# VS1053_hardware.net
KiCad netlist of a schematic drawn in EAGLE
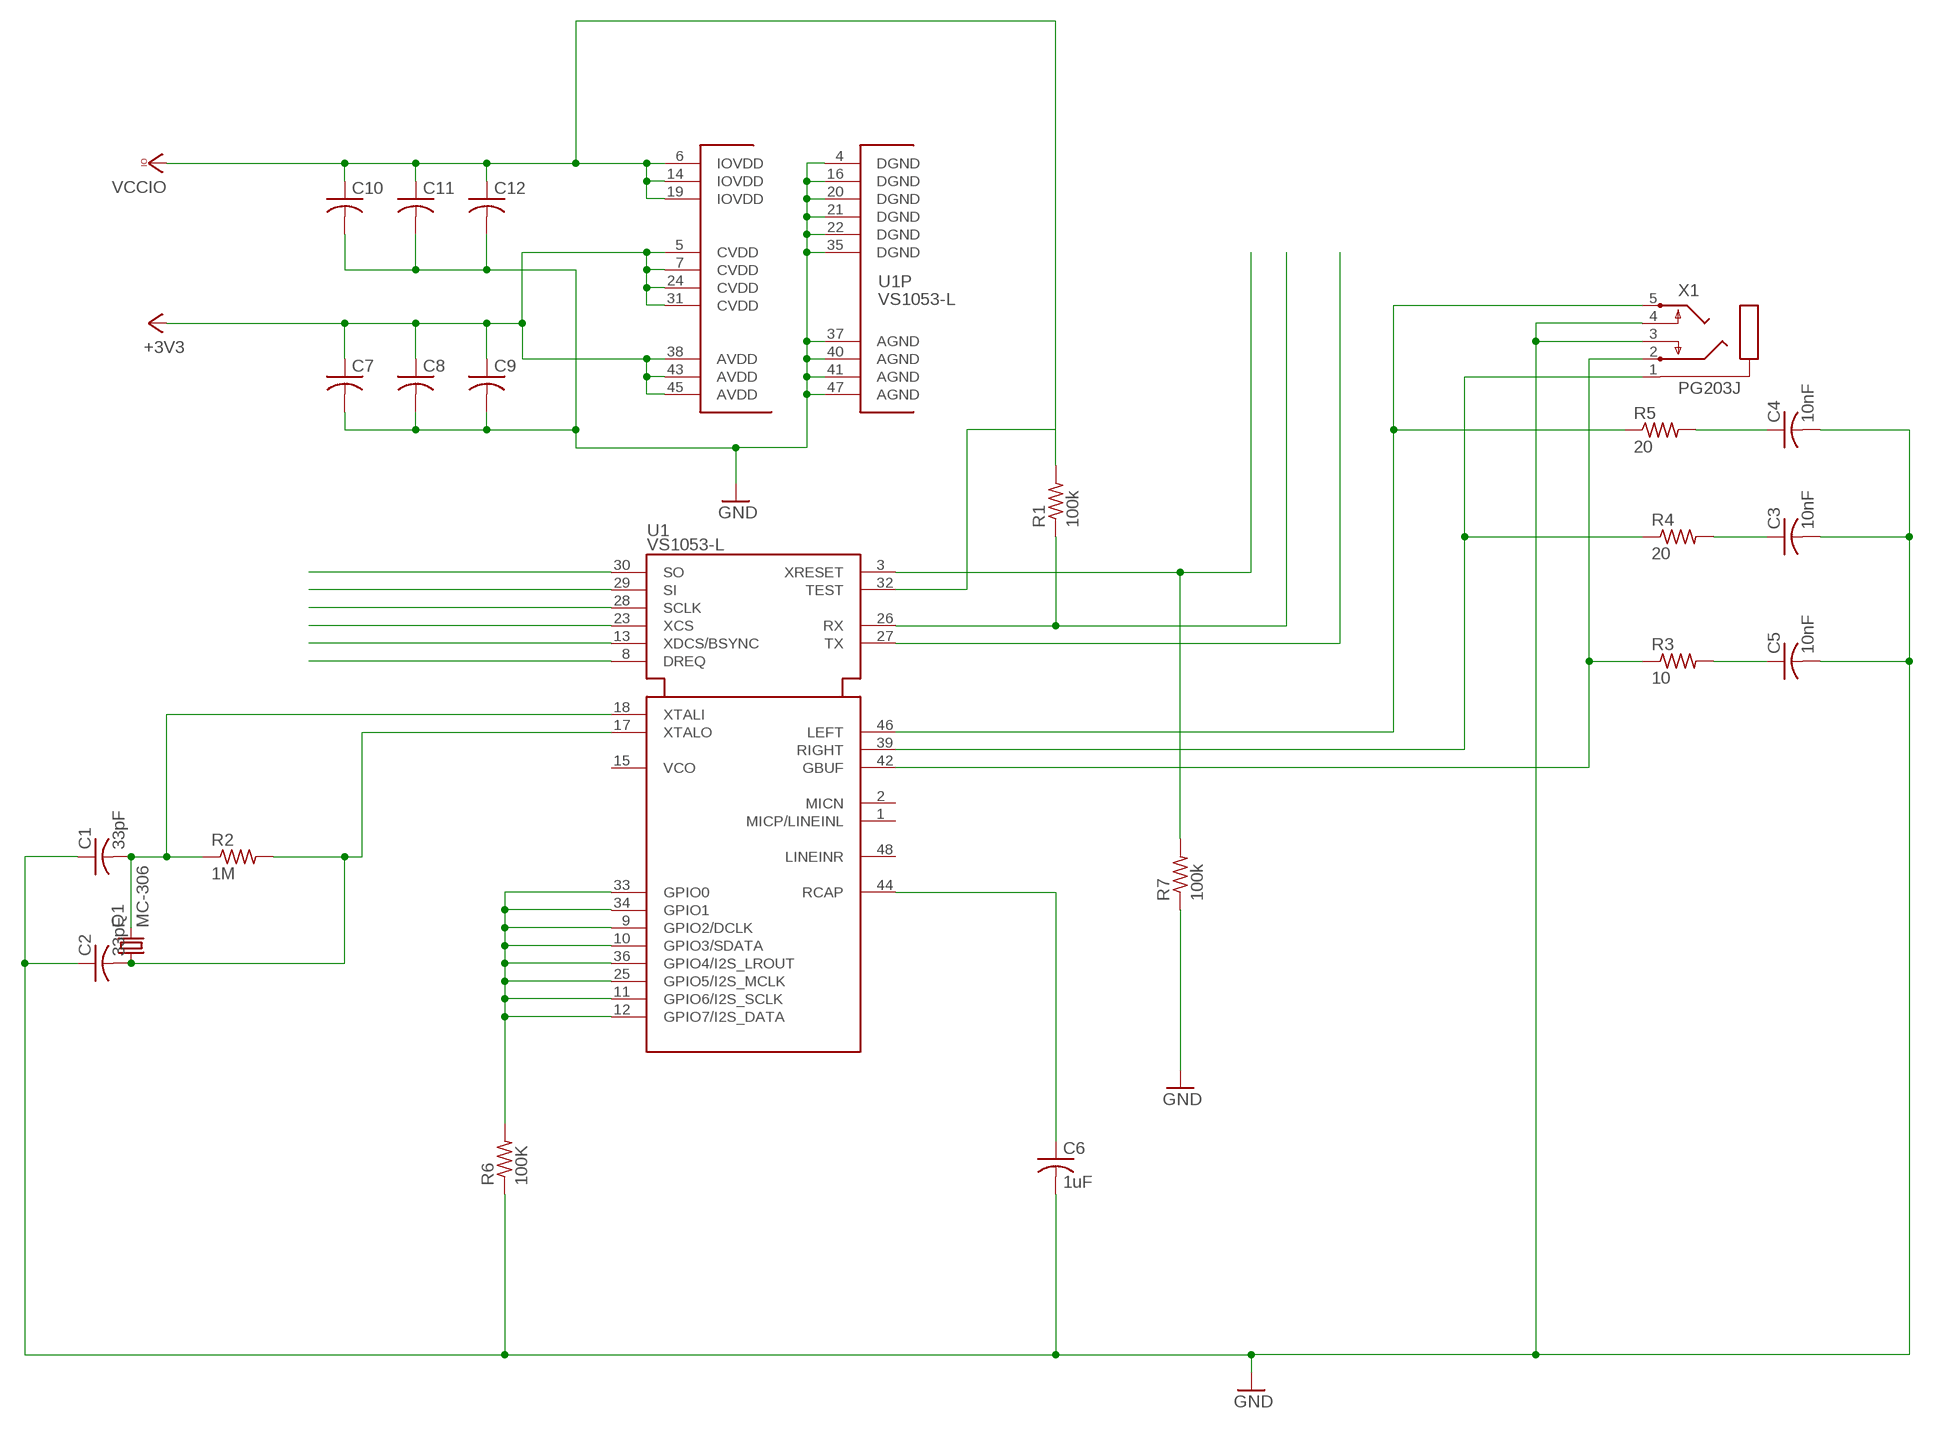
[diagram p0: schematic, sheet 1]

(export (version "E")
  (design (tool "Eeschema 10.0.6"))
  (components
    (comp (ref "C1")
      (value "33pF")
      (footprint "eagle-import:C0402")
      (libsource (lib "eagle-import") (part "C-USC0402"))
    )
    (comp (ref "C2")
      (value "33pF")
      (footprint "eagle-import:C0402")
      (libsource (lib "eagle-import") (part "C-USC0402"))
    )
    (comp (ref "C3")
      (value "10nF")
      (footprint "eagle-import:C0201")
      (libsource (lib "eagle-import") (part "C-USC0201"))
    )
    (comp (ref "C4")
      (value "10nF")
      (footprint "eagle-import:C0201")
      (libsource (lib "eagle-import") (part "C-USC0201"))
    )
    (comp (ref "C5")
      (value "10nF")
      (footprint "eagle-import:C0201")
      (libsource (lib "eagle-import") (part "C-USC0201"))
    )
    (comp (ref "C6")
      (value "1uF")
      (footprint "eagle-import:C0201")
      (libsource (lib "eagle-import") (part "C-USC0201"))
    )
    (comp (ref "C7")
      (value "C-USC0504")
      (footprint "eagle-import:C0504")
      (libsource (lib "eagle-import") (part "C-USC0504"))
    )
    (comp (ref "C8")
      (value "C-USC0504")
      (footprint "eagle-import:C0504")
      (libsource (lib "eagle-import") (part "C-USC0504"))
    )
    (comp (ref "C9")
      (value "C-USC0504")
      (footprint "eagle-import:C0504")
      (libsource (lib "eagle-import") (part "C-USC0504"))
    )
    (comp (ref "C10")
      (value "C-USC0504")
      (footprint "eagle-import:C0504")
      (libsource (lib "eagle-import") (part "C-USC0504"))
    )
    (comp (ref "C11")
      (value "C-USC0504")
      (footprint "eagle-import:C0504")
      (libsource (lib "eagle-import") (part "C-USC0504"))
    )
    (comp (ref "C12")
      (value "C-USC0504")
      (footprint "eagle-import:C0504")
      (libsource (lib "eagle-import") (part "C-USC0504"))
    )
    (comp (ref "Q1")
      (value "MC-306")
      (footprint "eagle-import:MC-306")
      (fields (field (name "MPN") "MC-306 60.0KHZ  100PPM ,12.5PF"))
      (libsource (lib "eagle-import") (part "MC-306"))
    )
    (comp (ref "R1")
      (value "100k")
      (footprint "eagle-import:M0805")
      (libsource (lib "eagle-import") (part "R-US_M0805"))
    )
    (comp (ref "R2")
      (value "1M")
      (footprint "eagle-import:1812X7R")
      (libsource (lib "eagle-import") (part "R-US_1812X7R"))
    )
    (comp (ref "R3")
      (value "10")
      (footprint "eagle-import:R01005")
      (libsource (lib "eagle-import") (part "R-US_01005"))
    )
    (comp (ref "R4")
      (value "20")
      (footprint "eagle-import:R01005")
      (libsource (lib "eagle-import") (part "R-US_01005"))
    )
    (comp (ref "R5")
      (value "20")
      (footprint "eagle-import:R01005")
      (libsource (lib "eagle-import") (part "R-US_01005"))
    )
    (comp (ref "R6")
      (value "100K")
      (footprint "eagle-import:M0805")
      (libsource (lib "eagle-import") (part "R-US_M0805"))
    )
    (comp (ref "R7")
      (value "100k")
      (footprint "eagle-import:M0805")
      (libsource (lib "eagle-import") (part "R-US_M0805"))
    )
    (comp (ref "U1")
      (value "VS1053-L")
      (footprint "eagle-import:LQFP48")
      (libsource (lib "eagle-import") (part "VS1053-L"))
    )
    (comp (ref "X1")
      (value "PG203J")
      (footprint "eagle-import:PG203J")
      (libsource (lib "eagle-import") (part "PG203J"))
    )
  )
  (nets
    (net (code "1") (name "+3V3") (class "Default")
      (node (ref "C7") (pin "1") (pinfunction "1_1") (pintype "passive"))
      (node (ref "C8") (pin "1") (pinfunction "1_1") (pintype "passive"))
      (node (ref "C9") (pin "1") (pinfunction "1_1") (pintype "passive"))
      (node (ref "U1") (pin "24") (pinfunction "CVDD_24") (pintype "power_in"))
      (node (ref "U1") (pin "31") (pinfunction "CVDD_31") (pintype "power_in"))
      (node (ref "U1") (pin "38") (pinfunction "AVDD_38") (pintype "power_in"))
      (node (ref "U1") (pin "43") (pinfunction "AVDD_43") (pintype "power_in"))
      (node (ref "U1") (pin "45") (pinfunction "AVDD_45") (pintype "power_in"))
      (node (ref "U1") (pin "5") (pinfunction "CVDD_5") (pintype "power_in"))
      (node (ref "U1") (pin "7") (pinfunction "CVDD_7") (pintype "power_in"))
    )
    (net (code "2") (name "GND") (class "Default")
      (node (ref "C1") (pin "1") (pinfunction "1_1") (pintype "passive"))
      (node (ref "C10") (pin "2") (pinfunction "2_2") (pintype "passive"))
      (node (ref "C11") (pin "2") (pinfunction "2_2") (pintype "passive"))
      (node (ref "C12") (pin "2") (pinfunction "2_2") (pintype "passive"))
      (node (ref "C2") (pin "1") (pinfunction "1_1") (pintype "passive"))
      (node (ref "C3") (pin "2") (pinfunction "2_2") (pintype "passive"))
      (node (ref "C4") (pin "2") (pinfunction "2_2") (pintype "passive"))
      (node (ref "C5") (pin "2") (pinfunction "2_2") (pintype "passive"))
      (node (ref "C6") (pin "2") (pinfunction "2_2") (pintype "passive"))
      (node (ref "C7") (pin "2") (pinfunction "2_2") (pintype "passive"))
      (node (ref "C8") (pin "2") (pinfunction "2_2") (pintype "passive"))
      (node (ref "C9") (pin "2") (pinfunction "2_2") (pintype "passive"))
      (node (ref "R6") (pin "1") (pinfunction "1_1") (pintype "passive"))
      (node (ref "R7") (pin "1") (pinfunction "1_1") (pintype "passive"))
      (node (ref "U1") (pin "16") (pinfunction "DGND_16") (pintype "power_in"))
      (node (ref "U1") (pin "20") (pinfunction "DGND_20") (pintype "power_in"))
      (node (ref "U1") (pin "21") (pinfunction "DGND_21") (pintype "power_in"))
      (node (ref "U1") (pin "22") (pinfunction "DGND_22") (pintype "power_in"))
      (node (ref "U1") (pin "35") (pinfunction "DGND_35") (pintype "power_in"))
      (node (ref "U1") (pin "37") (pinfunction "AGND_37") (pintype "power_in"))
      (node (ref "U1") (pin "4") (pinfunction "DGND_4") (pintype "power_in"))
      (node (ref "U1") (pin "40") (pinfunction "AGND_40") (pintype "power_in"))
      (node (ref "U1") (pin "41") (pinfunction "AGND_41") (pintype "power_in"))
      (node (ref "U1") (pin "47") (pinfunction "AGND_47") (pintype "power_in"))
      (node (ref "X1") (pin "3") (pinfunction "3_3") (pintype "passive"))
      (node (ref "X1") (pin "4") (pinfunction "4_4") (pintype "passive"))
    )
    (net (code "3") (name "Net-(C3-Pad1)") (class "Default")
      (node (ref "C3") (pin "1") (pinfunction "1_1") (pintype "passive"))
      (node (ref "R4") (pin "2") (pinfunction "2_2") (pintype "passive"))
    )
    (net (code "4") (name "Net-(C4-Pad1)") (class "Default")
      (node (ref "C4") (pin "1") (pinfunction "1_1") (pintype "passive"))
      (node (ref "R5") (pin "2") (pinfunction "2_2") (pintype "passive"))
    )
    (net (code "5") (name "Net-(C5-Pad1)") (class "Default")
      (node (ref "C5") (pin "1") (pinfunction "1_1") (pintype "passive"))
      (node (ref "R3") (pin "2") (pinfunction "2_2") (pintype "passive"))
    )
    (net (code "6") (name "Net-(Q1-2)") (class "Default")
      (node (ref "C1") (pin "2") (pinfunction "2_2") (pintype "passive"))
      (node (ref "Q1") (pin "4") (pinfunction "2_4") (pintype "passive"))
      (node (ref "R2") (pin "1") (pinfunction "1_1") (pintype "passive"))
      (node (ref "U1") (pin "18") (pinfunction "XTALI_18") (pintype "input"))
    )
    (net (code "7") (name "Net-(U1A-GBUF)") (class "Default")
      (node (ref "R3") (pin "1") (pinfunction "1_1") (pintype "passive"))
      (node (ref "U1") (pin "42") (pinfunction "GBUF_42") (pintype "output"))
      (node (ref "X1") (pin "2") (pinfunction "2_2") (pintype "passive"))
    )
    (net (code "8") (name "Net-(U1A-GPIO0)") (class "Default")
      (node (ref "R6") (pin "2") (pinfunction "2_2") (pintype "passive"))
      (node (ref "U1") (pin "10") (pinfunction "GPIO3/SDATA_10") (pintype "bidirectional"))
      (node (ref "U1") (pin "11") (pinfunction "GPIO6/I2S_SCLK_11") (pintype "bidirectional"))
      (node (ref "U1") (pin "12") (pinfunction "GPIO7/I2S_DATA_12") (pintype "bidirectional"))
      (node (ref "U1") (pin "25") (pinfunction "GPIO5/I2S_MCLK_25") (pintype "bidirectional"))
      (node (ref "U1") (pin "33") (pinfunction "GPIO0_33") (pintype "bidirectional"))
      (node (ref "U1") (pin "34") (pinfunction "GPIO1_34") (pintype "bidirectional"))
      (node (ref "U1") (pin "36") (pinfunction "GPIO4/I2S_LROUT_36") (pintype "bidirectional"))
      (node (ref "U1") (pin "9") (pinfunction "GPIO2/DCLK_9") (pintype "bidirectional"))
    )
    (net (code "9") (name "Net-(U1A-LEFT)") (class "Default")
      (node (ref "R5") (pin "1") (pinfunction "1_1") (pintype "passive"))
      (node (ref "U1") (pin "46") (pinfunction "LEFT_46") (pintype "output"))
      (node (ref "X1") (pin "5") (pinfunction "5_5") (pintype "passive"))
    )
    (net (code "10") (name "Net-(U1A-RCAP)") (class "Default")
      (node (ref "C6") (pin "1") (pinfunction "1_1") (pintype "passive"))
      (node (ref "U1") (pin "44") (pinfunction "RCAP_44") (pintype "bidirectional"))
    )
    (net (code "11") (name "Net-(U1A-RIGHT)") (class "Default")
      (node (ref "R4") (pin "1") (pinfunction "1_1") (pintype "passive"))
      (node (ref "U1") (pin "39") (pinfunction "RIGHT_39") (pintype "output"))
      (node (ref "X1") (pin "1") (pinfunction "1_1") (pintype "passive"))
    )
    (net (code "12") (name "Net-(U1A-RX)") (class "Default")
      (node (ref "R1") (pin "1") (pinfunction "1_1") (pintype "passive"))
      (node (ref "U1") (pin "26") (pinfunction "RX_26") (pintype "input"))
    )
    (net (code "13") (name "Net-(U1A-XRESET)") (class "Default")
      (node (ref "R7") (pin "2") (pinfunction "2_2") (pintype "passive"))
      (node (ref "U1") (pin "3") (pinfunction "XRESET_3") (pintype "input"))
    )
    (net (code "14") (name "Net-(U1A-XTALO)") (class "Default")
      (node (ref "C2") (pin "2") (pinfunction "2_2") (pintype "passive"))
      (node (ref "Q1") (pin "1") (pinfunction "1_1") (pintype "passive"))
      (node (ref "R2") (pin "2") (pinfunction "2_2") (pintype "passive"))
      (node (ref "U1") (pin "17") (pinfunction "XTALO_17") (pintype "output"))
    )
    (net (code "15") (name "VCCIO") (class "Default")
      (node (ref "C10") (pin "1") (pinfunction "1_1") (pintype "passive"))
      (node (ref "C11") (pin "1") (pinfunction "1_1") (pintype "passive"))
      (node (ref "C12") (pin "1") (pinfunction "1_1") (pintype "passive"))
      (node (ref "R1") (pin "2") (pinfunction "2_2") (pintype "passive"))
      (node (ref "U1") (pin "14") (pinfunction "IOVDD_14") (pintype "power_in"))
      (node (ref "U1") (pin "19") (pinfunction "IOVDD_19") (pintype "power_in"))
      (node (ref "U1") (pin "32") (pinfunction "TEST_32") (pintype "input"))
      (node (ref "U1") (pin "6") (pinfunction "IOVDD_6") (pintype "power_in"))
    )
    (net (code "16") (name "unconnected-(U1A-DREQ-Pad8)") (class "Default")
      (node (ref "U1") (pin "8") (pinfunction "DREQ_8") (pintype "output"))
    )
    (net (code "17") (name "unconnected-(U1A-LINEINR-Pad48)") (class "Default")
      (node (ref "U1") (pin "48") (pinfunction "LINEINR_48") (pintype "input"))
    )
    (net (code "18") (name "unconnected-(U1A-MICN-Pad2)") (class "Default")
      (node (ref "U1") (pin "2") (pinfunction "MICN_2") (pintype "input"))
    )
    (net (code "19") (name "unconnected-(U1A-MICP{slash}LINEINL-Pad1)") (class "Default")
      (node (ref "U1") (pin "1") (pinfunction "MICP/LINEINL_1") (pintype "input"))
    )
    (net (code "20") (name "unconnected-(U1A-SCLK-Pad28)") (class "Default")
      (node (ref "U1") (pin "28") (pinfunction "SCLK_28") (pintype "input"))
    )
    (net (code "21") (name "unconnected-(U1A-SI-Pad29)") (class "Default")
      (node (ref "U1") (pin "29") (pinfunction "SI_29") (pintype "input"))
    )
    (net (code "22") (name "unconnected-(U1A-SO-Pad30)") (class "Default")
      (node (ref "U1") (pin "30") (pinfunction "SO_30") (pintype "output"))
    )
    (net (code "23") (name "unconnected-(U1A-TX-Pad27)") (class "Default")
      (node (ref "U1") (pin "27") (pinfunction "TX_27") (pintype "output"))
    )
    (net (code "24") (name "unconnected-(U1A-VCO-Pad15)") (class "Default")
      (node (ref "U1") (pin "15") (pinfunction "VCO_15") (pintype "output"))
    )
    (net (code "25") (name "unconnected-(U1A-XCS-Pad23)") (class "Default")
      (node (ref "U1") (pin "23") (pinfunction "XCS_23") (pintype "input"))
    )
    (net (code "26") (name "unconnected-(U1A-XDCS{slash}BSYNC-Pad13)") (class "Default")
      (node (ref "U1") (pin "13") (pinfunction "XDCS/BSYNC_13") (pintype "input"))
    )
  )
)
